# ME433_PIC32_Schematic.net
KiCad netlist of a schematic drawn in EAGLE
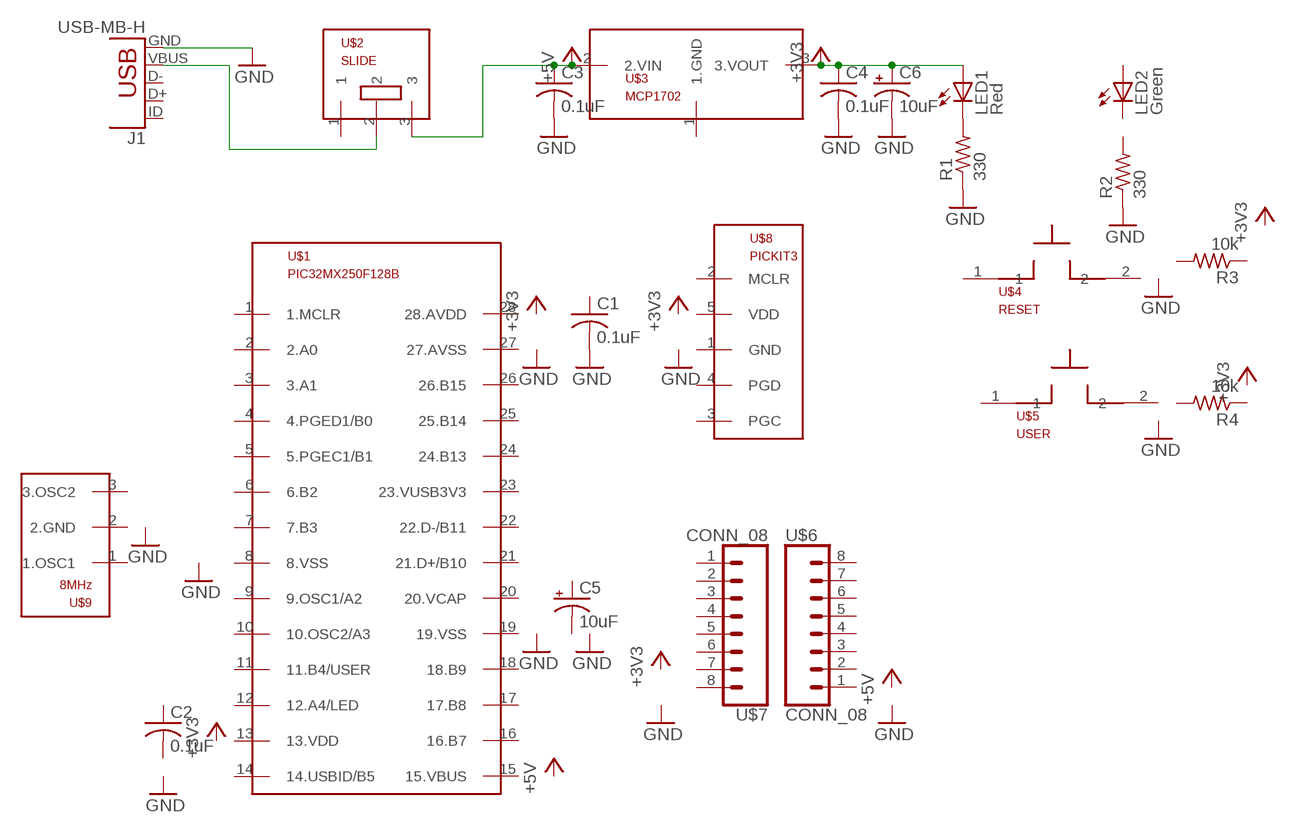
[diagram p0: schematic, sheet 1]

(export (version "E")
  (design (tool "Eeschema 10.0.6"))
  (components
    (comp (ref "C1")
      (value "0.1uF")
      (footprint "eagle-import:C025-025X050")
      (libsource (lib "eagle-import") (part "C-US025-025X050"))
    )
    (comp (ref "C2")
      (value "0.1uF")
      (footprint "eagle-import:C025-025X050")
      (libsource (lib "eagle-import") (part "C-US025-025X050"))
    )
    (comp (ref "C3")
      (value "0.1uF")
      (footprint "eagle-import:C025-025X050")
      (libsource (lib "eagle-import") (part "C-US025-025X050"))
    )
    (comp (ref "C4")
      (value "0.1uF")
      (footprint "eagle-import:C025-025X050")
      (libsource (lib "eagle-import") (part "C-US025-025X050"))
    )
    (comp (ref "C5")
      (value "10uF")
      (footprint "eagle-import:B45181B")
      (libsource (lib "eagle-import") (part "CPOL-USB45181B"))
    )
    (comp (ref "C6")
      (value "10uF")
      (footprint "eagle-import:B45181B")
      (libsource (lib "eagle-import") (part "CPOL-USB45181B"))
    )
    (comp (ref "J1")
      (value "USB-MB-H")
      (footprint "eagle-import:USB-MB-H")
      (libsource (lib "eagle-import") (part "USB-MB-H"))
    )
    (comp (ref "LED1")
      (value "Red")
      (footprint "eagle-import:LED3MM")
      (libsource (lib "eagle-import") (part "LED3MM"))
    )
    (comp (ref "LED2")
      (value "Green")
      (footprint "eagle-import:LED3MM")
      (libsource (lib "eagle-import") (part "LED3MM"))
    )
    (comp (ref "R1")
      (value "330")
      (footprint "eagle-import:0207_10")
      (libsource (lib "eagle-import") (part "R-US_0207/10"))
    )
    (comp (ref "R2")
      (value "330")
      (footprint "eagle-import:0207_10")
      (libsource (lib "eagle-import") (part "R-US_0207/10"))
    )
    (comp (ref "R3")
      (value "10k")
      (footprint "eagle-import:0207_10")
      (libsource (lib "eagle-import") (part "R-US_0207/10"))
    )
    (comp (ref "R4")
      (value "10k")
      (footprint "eagle-import:0207_10")
      (libsource (lib "eagle-import") (part "R-US_0207/10"))
    )
    (comp (ref "U$1")
      (value "PIC32MX250F128B")
      (footprint "eagle-import:DIL28-3")
      (libsource (lib "eagle-import") (part "PIC32MX250F128B"))
    )
    (comp (ref "U$2")
      (value "SLIDE")
      (footprint "eagle-import:SLIDE")
      (libsource (lib "eagle-import") (part "SLIDE"))
    )
    (comp (ref "U$3")
      (value "MCP1702")
      (footprint "eagle-import:TO92")
      (libsource (lib "eagle-import") (part "MCP1702"))
    )
    (comp (ref "U$4")
      (value "RESET")
      (footprint "eagle-import:PB")
      (libsource (lib "eagle-import") (part "PB"))
    )
    (comp (ref "U$5")
      (value "USER")
      (footprint "eagle-import:PB")
      (libsource (lib "eagle-import") (part "PB"))
    )
    (comp (ref "U$6")
      (value "CONN_08")
      (footprint "eagle-import:1X08")
      (libsource (lib "eagle-import") (part "CONN_08"))
    )
    (comp (ref "U$7")
      (value "CONN_08")
      (footprint "eagle-import:1X08")
      (libsource (lib "eagle-import") (part "CONN_08"))
    )
    (comp (ref "U$8")
      (value "PICKIT3")
      (footprint "eagle-import:1X05")
      (libsource (lib "eagle-import") (part "PICKIT3"))
    )
    (comp (ref "U$9")
      (value "8MHz")
      (footprint "eagle-import:OSC")
      (libsource (lib "eagle-import") (part "OSC"))
    )
  )
  (nets
    (net (code "1") (name "+3V3") (class "Default")
      (node (ref "C4") (pin "1") (pinfunction "1_1") (pintype "passive"))
      (node (ref "C6") (pin "+") (pinfunction "+_+") (pintype "passive"))
      (node (ref "LED1") (pin "A") (pinfunction "A_A") (pintype "passive"))
      (node (ref "U$3") (pin "3") (pinfunction "3.VOUT_3") (pintype "bidirectional"))
    )
    (net (code "2") (name "+5V") (class "Default")
      (node (ref "C3") (pin "1") (pinfunction "1_1") (pintype "passive"))
      (node (ref "U$2") (pin "3") (pinfunction "3_3") (pintype "bidirectional"))
      (node (ref "U$3") (pin "2") (pinfunction "2.VIN_2") (pintype "bidirectional"))
    )
    (net (code "3") (name "GND") (class "Default")
      (node (ref "C1") (pin "2") (pinfunction "2_2") (pintype "passive"))
      (node (ref "C3") (pin "2") (pinfunction "2_2") (pintype "passive"))
      (node (ref "C4") (pin "2") (pinfunction "2_2") (pintype "passive"))
      (node (ref "C6") (pin "-") (pinfunction "-_-") (pintype "passive"))
      (node (ref "J1") (pin "GND") (pinfunction "GND_GND") (pintype "bidirectional"))
      (node (ref "R1") (pin "1") (pinfunction "1_1") (pintype "passive"))
      (node (ref "R2") (pin "1") (pinfunction "1_1") (pintype "passive"))
    )
    (net (code "4") (name "Net-(J1-PadVBUS)") (class "Default")
      (node (ref "J1") (pin "VBUS") (pinfunction "VBUS_VBUS") (pintype "bidirectional"))
      (node (ref "U$2") (pin "2") (pinfunction "2_2") (pintype "bidirectional"))
    )
    (net (code "5") (name "Net-(LED1-C)") (class "Default")
      (node (ref "LED1") (pin "K") (pinfunction "C_K") (pintype "passive"))
      (node (ref "R1") (pin "2") (pinfunction "2_2") (pintype "passive"))
    )
    (net (code "6") (name "unconnected-(C1-Pad1)") (class "Default")
      (node (ref "C1") (pin "1") (pinfunction "1_1") (pintype "passive"))
    )
    (net (code "7") (name "unconnected-(C2-Pad1)") (class "Default")
      (node (ref "C2") (pin "1") (pinfunction "1_1") (pintype "passive"))
    )
    (net (code "8") (name "unconnected-(C2-Pad2)") (class "Default")
      (node (ref "C2") (pin "2") (pinfunction "2_2") (pintype "passive"))
    )
    (net (code "9") (name "unconnected-(C5-Pad+)") (class "Default")
      (node (ref "C5") (pin "+") (pinfunction "+_+") (pintype "passive"))
    )
    (net (code "10") (name "unconnected-(C5-Pad-)") (class "Default")
      (node (ref "C5") (pin "-") (pinfunction "-_-") (pintype "passive"))
    )
    (net (code "11") (name "unconnected-(J1-PadD+)") (class "Default")
      (node (ref "J1") (pin "D+") (pinfunction "D+_D+") (pintype "bidirectional"))
    )
    (net (code "12") (name "unconnected-(J1-PadD-)") (class "Default")
      (node (ref "J1") (pin "D-") (pinfunction "D-_D-") (pintype "bidirectional"))
    )
    (net (code "13") (name "unconnected-(J1-PadID)") (class "Default")
      (node (ref "J1") (pin "ID") (pinfunction "ID_ID") (pintype "bidirectional"))
    )
    (net (code "14") (name "unconnected-(LED2-C-PadK)") (class "Default")
      (node (ref "LED2") (pin "K") (pinfunction "C_K") (pintype "passive"))
    )
    (net (code "15") (name "unconnected-(LED2-PadA)") (class "Default")
      (node (ref "LED2") (pin "A") (pinfunction "A_A") (pintype "passive"))
    )
    (net (code "16") (name "unconnected-(R2-Pad2)") (class "Default")
      (node (ref "R2") (pin "2") (pinfunction "2_2") (pintype "passive"))
    )
    (net (code "17") (name "unconnected-(R3-Pad1)") (class "Default")
      (node (ref "R3") (pin "1") (pinfunction "1_1") (pintype "passive"))
    )
    (net (code "18") (name "unconnected-(R3-Pad2)") (class "Default")
      (node (ref "R3") (pin "2") (pinfunction "2_2") (pintype "passive"))
    )
    (net (code "19") (name "unconnected-(R4-Pad1)") (class "Default")
      (node (ref "R4") (pin "1") (pinfunction "1_1") (pintype "passive"))
    )
    (net (code "20") (name "unconnected-(R4-Pad2)") (class "Default")
      (node (ref "R4") (pin "2") (pinfunction "2_2") (pintype "passive"))
    )
    (net (code "21") (name "unconnected-(U$1-1.MCLR-Pad1)") (class "Default")
      (node (ref "U$1") (pin "1") (pinfunction "1.MCLR_1") (pintype "bidirectional"))
    )
    (net (code "22") (name "unconnected-(U$1-2.A0-Pad2)") (class "Default")
      (node (ref "U$1") (pin "2") (pinfunction "2.A0_2") (pintype "bidirectional"))
    )
    (net (code "23") (name "unconnected-(U$1-3.A1-Pad3)") (class "Default")
      (node (ref "U$1") (pin "3") (pinfunction "3.A1_3") (pintype "bidirectional"))
    )
    (net (code "24") (name "unconnected-(U$1-4.PGED1{slash}B0-Pad4)") (class "Default")
      (node (ref "U$1") (pin "4") (pinfunction "4.PGED1/B0_4") (pintype "bidirectional"))
    )
    (net (code "25") (name "unconnected-(U$1-5.PGEC1{slash}B1-Pad5)") (class "Default")
      (node (ref "U$1") (pin "5") (pinfunction "5.PGEC1/B1_5") (pintype "bidirectional"))
    )
    (net (code "26") (name "unconnected-(U$1-6.B2-Pad6)") (class "Default")
      (node (ref "U$1") (pin "6") (pinfunction "6.B2_6") (pintype "bidirectional"))
    )
    (net (code "27") (name "unconnected-(U$1-7.B3-Pad7)") (class "Default")
      (node (ref "U$1") (pin "7") (pinfunction "7.B3_7") (pintype "bidirectional"))
    )
    (net (code "28") (name "unconnected-(U$1-8.VSS-Pad8)") (class "Default")
      (node (ref "U$1") (pin "8") (pinfunction "8.VSS_8") (pintype "bidirectional"))
    )
    (net (code "29") (name "unconnected-(U$1-9.OSC1{slash}A2-Pad9)") (class "Default")
      (node (ref "U$1") (pin "9") (pinfunction "9.OSC1/A2_9") (pintype "bidirectional"))
    )
    (net (code "30") (name "unconnected-(U$1-10.OSC2{slash}A3-Pad10)") (class "Default")
      (node (ref "U$1") (pin "10") (pinfunction "10.OSC2/A3_10") (pintype "bidirectional"))
    )
    (net (code "31") (name "unconnected-(U$1-11.B4{slash}USER-Pad11)") (class "Default")
      (node (ref "U$1") (pin "11") (pinfunction "11.B4/USER_11") (pintype "bidirectional"))
    )
    (net (code "32") (name "unconnected-(U$1-12.A4{slash}LED-Pad12)") (class "Default")
      (node (ref "U$1") (pin "12") (pinfunction "12.A4/LED_12") (pintype "bidirectional"))
    )
    (net (code "33") (name "unconnected-(U$1-13.VDD-Pad13)") (class "Default")
      (node (ref "U$1") (pin "13") (pinfunction "13.VDD_13") (pintype "bidirectional"))
    )
    (net (code "34") (name "unconnected-(U$1-14.USBID{slash}B5-Pad14)") (class "Default")
      (node (ref "U$1") (pin "14") (pinfunction "14.USBID/B5_14") (pintype "bidirectional"))
    )
    (net (code "35") (name "unconnected-(U$1-15.VBUS-Pad15)") (class "Default")
      (node (ref "U$1") (pin "15") (pinfunction "15.VBUS_15") (pintype "bidirectional"))
    )
    (net (code "36") (name "unconnected-(U$1-16.B7-Pad16)") (class "Default")
      (node (ref "U$1") (pin "16") (pinfunction "16.B7_16") (pintype "bidirectional"))
    )
    (net (code "37") (name "unconnected-(U$1-17.B8-Pad17)") (class "Default")
      (node (ref "U$1") (pin "17") (pinfunction "17.B8_17") (pintype "bidirectional"))
    )
    (net (code "38") (name "unconnected-(U$1-18.B9-Pad18)") (class "Default")
      (node (ref "U$1") (pin "18") (pinfunction "18.B9_18") (pintype "bidirectional"))
    )
    (net (code "39") (name "unconnected-(U$1-19.VSS-Pad19)") (class "Default")
      (node (ref "U$1") (pin "19") (pinfunction "19.VSS_19") (pintype "bidirectional"))
    )
    (net (code "40") (name "unconnected-(U$1-20.VCAP-Pad20)") (class "Default")
      (node (ref "U$1") (pin "20") (pinfunction "20.VCAP_20") (pintype "bidirectional"))
    )
    (net (code "41") (name "unconnected-(U$1-21.D+{slash}B10-Pad21)") (class "Default")
      (node (ref "U$1") (pin "21") (pinfunction "21.D+/B10_21") (pintype "bidirectional"))
    )
    (net (code "42") (name "unconnected-(U$1-22.D-{slash}B11-Pad22)") (class "Default")
      (node (ref "U$1") (pin "22") (pinfunction "22.D-/B11_22") (pintype "bidirectional"))
    )
    (net (code "43") (name "unconnected-(U$1-23.VUSB3V3-Pad23)") (class "Default")
      (node (ref "U$1") (pin "23") (pinfunction "23.VUSB3V3_23") (pintype "bidirectional"))
    )
    (net (code "44") (name "unconnected-(U$1-24.B13-Pad24)") (class "Default")
      (node (ref "U$1") (pin "24") (pinfunction "24.B13_24") (pintype "bidirectional"))
    )
    (net (code "45") (name "unconnected-(U$1-25.B14-Pad25)") (class "Default")
      (node (ref "U$1") (pin "25") (pinfunction "25.B14_25") (pintype "bidirectional"))
    )
    (net (code "46") (name "unconnected-(U$1-26.B15-Pad26)") (class "Default")
      (node (ref "U$1") (pin "26") (pinfunction "26.B15_26") (pintype "bidirectional"))
    )
    (net (code "47") (name "unconnected-(U$1-27.AVSS-Pad27)") (class "Default")
      (node (ref "U$1") (pin "27") (pinfunction "27.AVSS_27") (pintype "bidirectional"))
    )
    (net (code "48") (name "unconnected-(U$1-28.AVDD-Pad28)") (class "Default")
      (node (ref "U$1") (pin "28") (pinfunction "28.AVDD_28") (pintype "bidirectional"))
    )
    (net (code "49") (name "unconnected-(U$2-Pad1)") (class "Default")
      (node (ref "U$2") (pin "1") (pinfunction "1_1") (pintype "bidirectional"))
    )
    (net (code "50") (name "unconnected-(U$3-1.GND-Pad1)") (class "Default")
      (node (ref "U$3") (pin "1") (pinfunction "1.GND_1") (pintype "bidirectional"))
    )
    (net (code "51") (name "unconnected-(U$4-Pad1)") (class "Default")
      (node (ref "U$4") (pin "1") (pinfunction "1_1") (pintype "bidirectional"))
    )
    (net (code "52") (name "unconnected-(U$4-Pad2)") (class "Default")
      (node (ref "U$4") (pin "2") (pinfunction "2_2") (pintype "bidirectional"))
    )
    (net (code "53") (name "unconnected-(U$5-Pad1)") (class "Default")
      (node (ref "U$5") (pin "1") (pinfunction "1_1") (pintype "bidirectional"))
    )
    (net (code "54") (name "unconnected-(U$5-Pad2)") (class "Default")
      (node (ref "U$5") (pin "2") (pinfunction "2_2") (pintype "bidirectional"))
    )
    (net (code "55") (name "unconnected-(U$6-Pad1)") (class "Default")
      (node (ref "U$6") (pin "1") (pinfunction "1_1") (pintype "passive"))
    )
    (net (code "56") (name "unconnected-(U$6-Pad2)") (class "Default")
      (node (ref "U$6") (pin "2") (pinfunction "2_2") (pintype "passive"))
    )
    (net (code "57") (name "unconnected-(U$6-Pad3)") (class "Default")
      (node (ref "U$6") (pin "3") (pinfunction "3_3") (pintype "passive"))
    )
    (net (code "58") (name "unconnected-(U$6-Pad4)") (class "Default")
      (node (ref "U$6") (pin "4") (pinfunction "4_4") (pintype "passive"))
    )
    (net (code "59") (name "unconnected-(U$6-Pad5)") (class "Default")
      (node (ref "U$6") (pin "5") (pinfunction "5_5") (pintype "passive"))
    )
    (net (code "60") (name "unconnected-(U$6-Pad6)") (class "Default")
      (node (ref "U$6") (pin "6") (pinfunction "6_6") (pintype "passive"))
    )
    (net (code "61") (name "unconnected-(U$6-Pad7)") (class "Default")
      (node (ref "U$6") (pin "7") (pinfunction "7_7") (pintype "passive"))
    )
    (net (code "62") (name "unconnected-(U$6-Pad8)") (class "Default")
      (node (ref "U$6") (pin "8") (pinfunction "8_8") (pintype "passive"))
    )
    (net (code "63") (name "unconnected-(U$7-Pad1)") (class "Default")
      (node (ref "U$7") (pin "1") (pinfunction "1_1") (pintype "passive"))
    )
    (net (code "64") (name "unconnected-(U$7-Pad2)") (class "Default")
      (node (ref "U$7") (pin "2") (pinfunction "2_2") (pintype "passive"))
    )
    (net (code "65") (name "unconnected-(U$7-Pad3)") (class "Default")
      (node (ref "U$7") (pin "3") (pinfunction "3_3") (pintype "passive"))
    )
    (net (code "66") (name "unconnected-(U$7-Pad4)") (class "Default")
      (node (ref "U$7") (pin "4") (pinfunction "4_4") (pintype "passive"))
    )
    (net (code "67") (name "unconnected-(U$7-Pad5)") (class "Default")
      (node (ref "U$7") (pin "5") (pinfunction "5_5") (pintype "passive"))
    )
    (net (code "68") (name "unconnected-(U$7-Pad6)") (class "Default")
      (node (ref "U$7") (pin "6") (pinfunction "6_6") (pintype "passive"))
    )
    (net (code "69") (name "unconnected-(U$7-Pad7)") (class "Default")
      (node (ref "U$7") (pin "7") (pinfunction "7_7") (pintype "passive"))
    )
    (net (code "70") (name "unconnected-(U$7-Pad8)") (class "Default")
      (node (ref "U$7") (pin "8") (pinfunction "8_8") (pintype "passive"))
    )
    (net (code "71") (name "unconnected-(U$8-GND-Pad1)") (class "Default")
      (node (ref "U$8") (pin "1") (pinfunction "GND_1") (pintype "bidirectional"))
    )
    (net (code "72") (name "unconnected-(U$8-MCLR-Pad2)") (class "Default")
      (node (ref "U$8") (pin "2") (pinfunction "MCLR_2") (pintype "bidirectional"))
    )
    (net (code "73") (name "unconnected-(U$8-PGC-Pad3)") (class "Default")
      (node (ref "U$8") (pin "3") (pinfunction "PGC_3") (pintype "bidirectional"))
    )
    (net (code "74") (name "unconnected-(U$8-PGD-Pad4)") (class "Default")
      (node (ref "U$8") (pin "4") (pinfunction "PGD_4") (pintype "bidirectional"))
    )
    (net (code "75") (name "unconnected-(U$8-VDD-Pad5)") (class "Default")
      (node (ref "U$8") (pin "5") (pinfunction "VDD_5") (pintype "bidirectional"))
    )
    (net (code "76") (name "unconnected-(U$9-1.OSC1-Pad1)") (class "Default")
      (node (ref "U$9") (pin "1") (pinfunction "1.OSC1_1") (pintype "bidirectional"))
    )
    (net (code "77") (name "unconnected-(U$9-2.GND-Pad2)") (class "Default")
      (node (ref "U$9") (pin "2") (pinfunction "2.GND_2") (pintype "bidirectional"))
    )
    (net (code "78") (name "unconnected-(U$9-3.OSC2-Pad3)") (class "Default")
      (node (ref "U$9") (pin "3") (pinfunction "3.OSC2_3") (pintype "bidirectional"))
    )
  )
)
